# Sheet1.net
KiCad netlist of a schematic drawn in Altium Designer
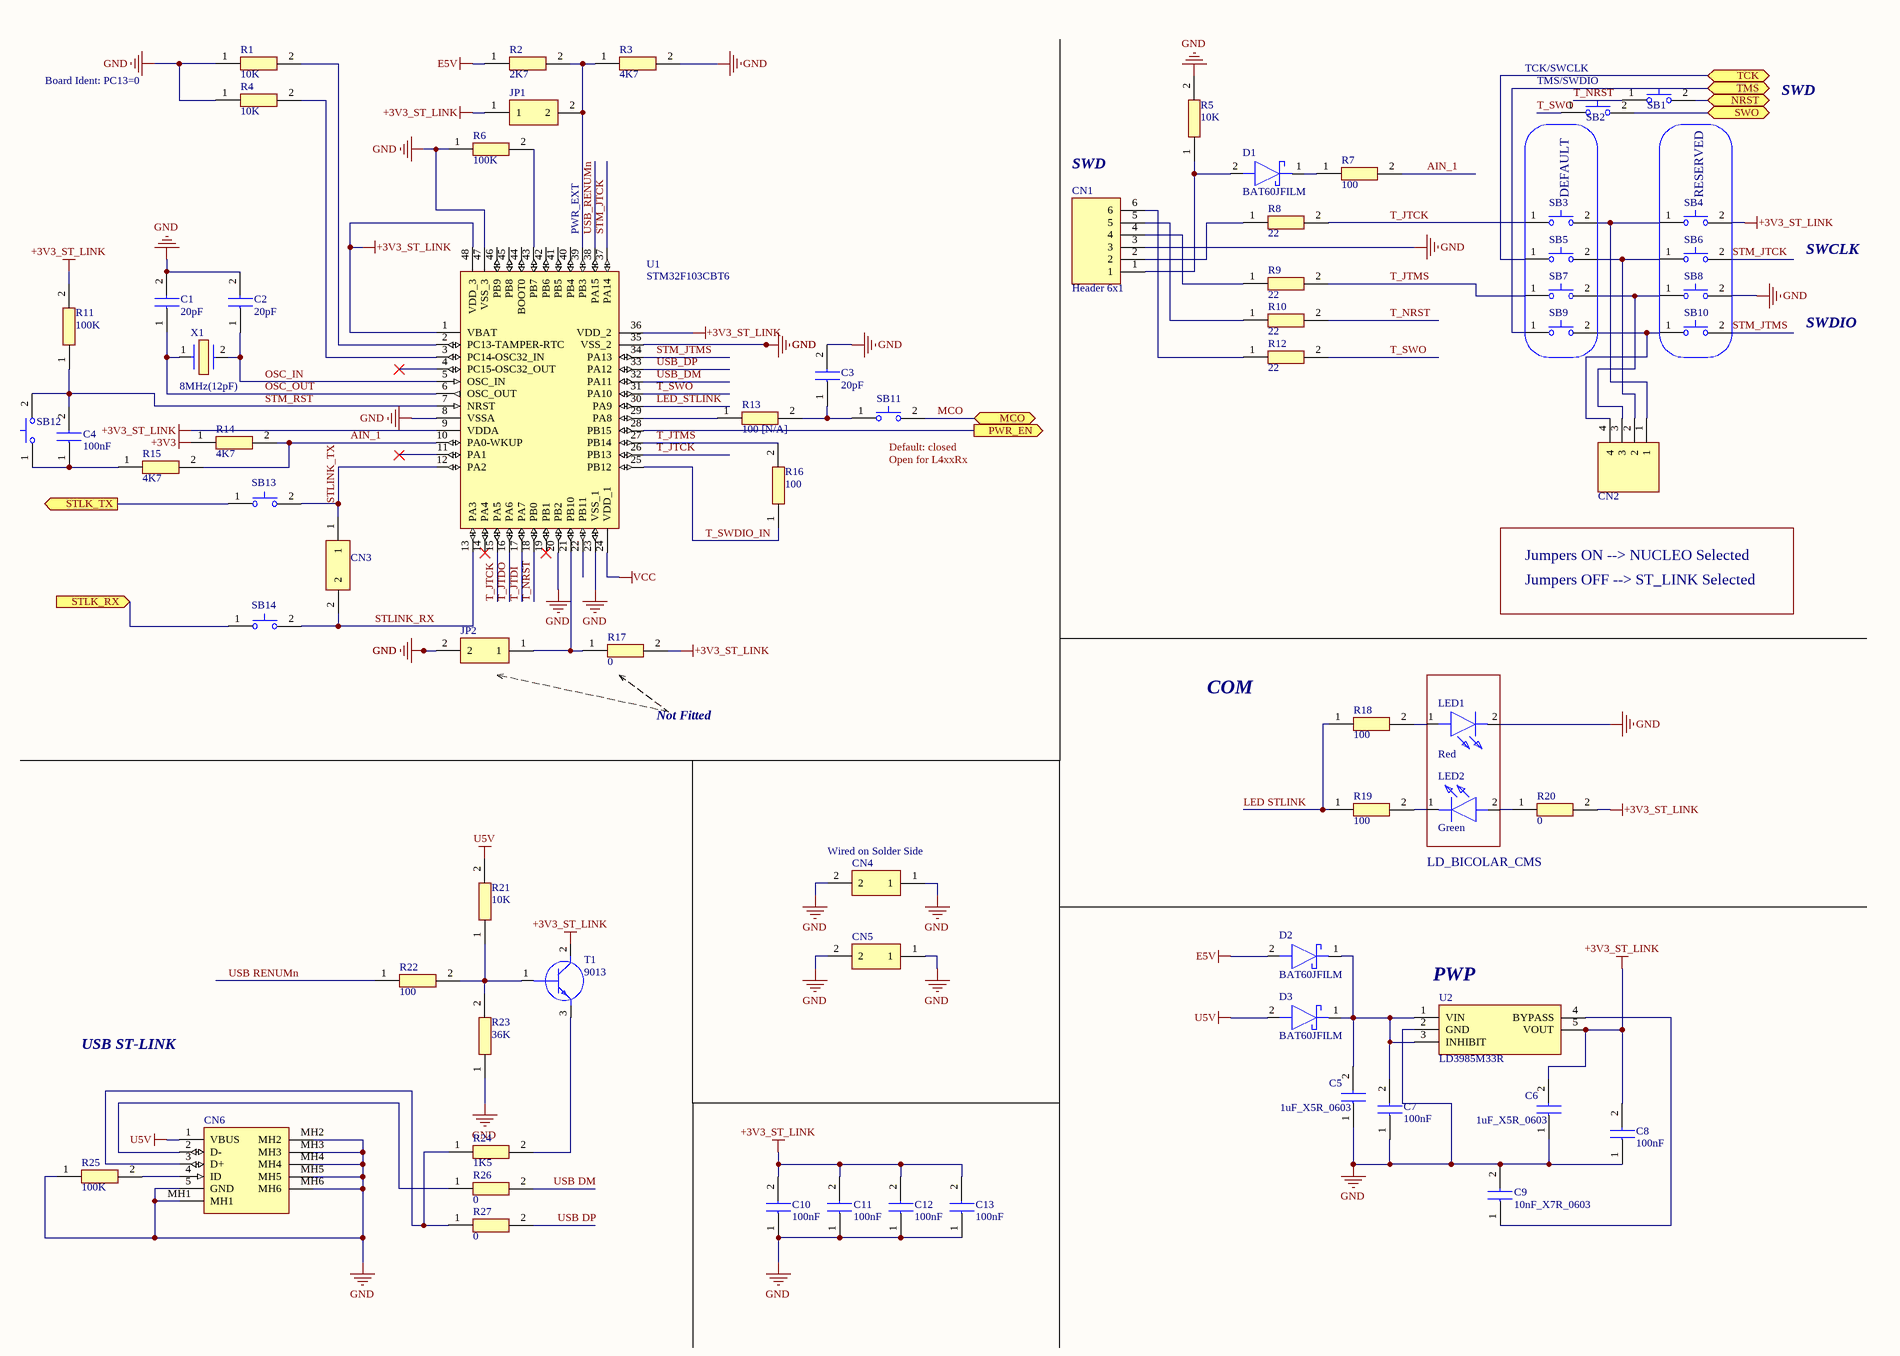
[diagram p0: Sheet1.SchDoc, right]

(export (version "E")
  (design (tool "Eeschema 10.0.6"))
  (components
    (comp (ref "C1")
      (value "20pF")
      (footprint "SamacSys:C1206")
      (description "Capacitor")
      (fields (field (name "MANUFACTURER_PART_NUMBER") "C1206C200KCGACTU"))
      (libsource (lib "*") (part "C1206C200KCGACTU"))
    )
    (comp (ref "C2")
      (value "20pF")
      (footprint "SamacSys:C1206")
      (description "Capacitor")
      (fields (field (name "MANUFACTURER_PART_NUMBER") "C1206C200KCGACTU"))
      (libsource (lib "*") (part "C1206C200KCGACTU"))
    )
    (comp (ref "C3")
      (value "20pF")
      (footprint "SamacSys:C1206")
      (description "Capacitor")
      (fields (field (name "MANUFACTURER_PART_NUMBER") "C1206C200KCGACTU"))
      (libsource (lib "*") (part "C1206C200KCGACTU"))
    )
    (comp (ref "C4")
      (value "100nF")
      (footprint "SamacSys:CAPC1608X90N")
      (description "Capacitor")
      (fields
        (field (name "MANUFACTURER_PART_NUMBER") "KAM15AR71H104KM")
        (field (name "MOUSER PART NUMBER") "581-KAM15AR71H104KM")
      )
      (libsource (lib "*") (part "KAM15AR71H104KM"))
    )
    (comp (ref "C5")
      (value "1uF_X5R_0603")
      (footprint "SamacSys:MAJx16")
      (description "Capacitor")
      (fields (field (name "MANUFACTURER_PART_NUMBER") "MAJCT168BB7105KTEA01"))
      (libsource (lib "*") (part "MAJCT168BB7105KTEA01"))
    )
    (comp (ref "C6")
      (value "1uF_X5R_0603")
      (footprint "SamacSys:MAJx16")
      (description "Capacitor")
      (fields (field (name "MANUFACTURER_PART_NUMBER") "MAJCT168BB7105KTEA01"))
      (libsource (lib "*") (part "MAJCT168BB7105KTEA01"))
    )
    (comp (ref "C7")
      (value "100nF")
      (footprint "SamacSys:CAPC1608X90N")
      (description "Capacitor")
      (fields
        (field (name "MANUFACTURER_PART_NUMBER") "KAM15AR71H104KM")
        (field (name "MOUSER PART NUMBER") "581-KAM15AR71H104KM")
      )
      (libsource (lib "*") (part "KAM15AR71H104KM"))
    )
    (comp (ref "C8")
      (value "100nF")
      (footprint "SamacSys:CAPC1608X90N")
      (description "Capacitor")
      (fields
        (field (name "MANUFACTURER_PART_NUMBER") "KAM15AR71H104KM")
        (field (name "MOUSER PART NUMBER") "581-KAM15AR71H104KM")
      )
      (libsource (lib "*") (part "KAM15AR71H104KM"))
    )
    (comp (ref "C9")
      (value "10nF_X7R_0603")
      (footprint "SamacSys:CAPC3316X145N")
      (description "Capacitor")
      (fields
        (field (name "MANUFACTURER_PART_NUMBER") "KGM31GCG2J103JU")
        (field (name "MOUSER PART NUMBER") "581-KGM31GCG2J103JU")
      )
      (libsource (lib "*") (part "KGM31GCG2J103JU"))
    )
    (comp (ref "C10")
      (value "100nF")
      (footprint "SamacSys:CAPC1608X90N")
      (description "Capacitor")
      (fields
        (field (name "MANUFACTURER_PART_NUMBER") "KAM15AR71H104KM")
        (field (name "MOUSER PART NUMBER") "581-KAM15AR71H104KM")
      )
      (libsource (lib "*") (part "KAM15AR71H104KM"))
    )
    (comp (ref "C11")
      (value "100nF")
      (footprint "SamacSys:CAPC1608X90N")
      (description "Capacitor")
      (fields
        (field (name "MANUFACTURER_PART_NUMBER") "KAM15AR71H104KM")
        (field (name "MOUSER PART NUMBER") "581-KAM15AR71H104KM")
      )
      (libsource (lib "*") (part "KAM15AR71H104KM"))
    )
    (comp (ref "C12")
      (value "100nF")
      (footprint "SamacSys:CAPC1608X90N")
      (description "Capacitor")
      (fields
        (field (name "MANUFACTURER_PART_NUMBER") "KAM15AR71H104KM")
        (field (name "MOUSER PART NUMBER") "581-KAM15AR71H104KM")
      )
      (libsource (lib "*") (part "KAM15AR71H104KM"))
    )
    (comp (ref "C13")
      (value "100nF")
      (footprint "SamacSys:CAPC1608X90N")
      (description "Capacitor")
      (fields
        (field (name "MANUFACTURER_PART_NUMBER") "KAM15AR71H104KM")
        (field (name "MOUSER PART NUMBER") "581-KAM15AR71H104KM")
      )
      (libsource (lib "*") (part "KAM15AR71H104KM"))
    )
    (comp (ref "CN1")
      (value "Header 6x1")
      (footprint "SamacSys:HDRV6W66P0X254_1X6_1524X249X838P")
      (description "Connector")
      (fields
        (field (name "MANUFACTURER_PART_NUMBER") "22-28-4062")
        (field (name "MOUSER PART NUMBER") "538-22-28-4062")
      )
      (libsource (lib "*") (part "22-28-4062"))
    )
    (comp (ref "CN2")
      (value "53014-0410")
      (footprint "SamacSys:SHDR4W60P0X200_1X4_1200X435X1000P")
      (description "Connector")
      (fields (field (name "MOUSER PART NUMBER") "538-53014-0410"))
      (libsource (lib "*") (part "53014-0410"))
    )
    (comp (ref "CN3")
      (value "3-647166-2")
      (footprint "SamacSys:36471662")
      (description "Connector")
      (fields (field (name "MOUSER PART NUMBER") "571-3-647166-2"))
      (libsource (lib "") (part "3-647166-2_1"))
    )
    (comp (ref "CN4")
      (value "3-647166-2")
      (footprint "SamacSys:36471662")
      (description "Connector")
      (fields (field (name "MOUSER PART NUMBER") "571-3-647166-2"))
      (libsource (lib "*") (part "3-647166-2"))
    )
    (comp (ref "CN5")
      (value "3-647166-2")
      (footprint "SamacSys:36471662")
      (description "Connector")
      (fields (field (name "MOUSER PART NUMBER") "571-3-647166-2"))
      (libsource (lib "*") (part "3-647166-2"))
    )
    (comp (ref "CN6")
      (value "204926-1103")
      (footprint "SamacSys:2049261103")
      (description "Connector")
      (fields (field (name "MOUSER PART NUMBER") "538-204926-1103"))
      (libsource (lib "*") (part "204926-1103"))
    )
    (comp (ref "D1")
      (value "BAT60JFILM")
      (footprint "SamacSys:SOD2513X117N")
      (description "Schottky Diode")
      (fields (field (name "MOUSER PART NUMBER") "511-BAT60JFILM"))
      (libsource (lib "*") (part "BAT60JFILM"))
    )
    (comp (ref "D2")
      (value "BAT60JFILM")
      (footprint "SamacSys:SOD2513X117N")
      (description "Schottky Diode")
      (fields (field (name "MOUSER PART NUMBER") "511-BAT60JFILM"))
      (libsource (lib "*") (part "BAT60JFILM"))
    )
    (comp (ref "D3")
      (value "BAT60JFILM")
      (footprint "SamacSys:SOD2513X117N")
      (description "Schottky Diode")
      (fields (field (name "MOUSER PART NUMBER") "511-BAT60JFILM"))
      (libsource (lib "*") (part "BAT60JFILM"))
    )
    (comp (ref "JP1")
      (value "3-647166-2")
      (footprint "SamacSys:36471662")
      (description "Connector")
      (fields (field (name "MOUSER PART NUMBER") "571-3-647166-2"))
      (libsource (lib "") (part "3-647166-2_2"))
    )
    (comp (ref "JP2")
      (value "3-647166-2")
      (footprint "SamacSys:36471662")
      (description "Connector")
      (fields (field (name "MOUSER PART NUMBER") "571-3-647166-2"))
      (libsource (lib "*") (part "3-647166-2"))
    )
    (comp (ref "LED1")
      (value "Red")
      (footprint "SamacSys:C4SMARGYCS4V1BB1")
      (description "LED")
      (fields
        (field (name "MANUFACTURER_PART_NUMBER") "C4SMA-RGY-CS4V1BB1")
        (field (name "MOUSER PART NUMBER") "941-C4SMARGYCS4V1BB1")
      )
      (libsource (lib "*") (part "C4SMA-RGY-CS4V1BB1"))
    )
    (comp (ref "LED2")
      (value "Green")
      (footprint "SamacSys:TLHG5420ASZ")
      (description "LED")
      (fields
        (field (name "MANUFACTURER_PART_NUMBER") "TLHG5420-ASZ")
        (field (name "MOUSER PART NUMBER") "78-TLHG5420-ASZ")
      )
      (libsource (lib "*") (part "TLHG5420-ASZ"))
    )
    (comp (ref "R1")
      (value "10K")
      (footprint "SamacSys:RESC6331X80N")
      (description "Resistor")
      (fields
        (field (name "MANUFACTURER_PART_NUMBER") "CRM2512QJW-103ELF")
        (field (name "MOUSER PART NUMBER") "652-CRM2512QJW-103E")
      )
      (libsource (lib "*") (part "CRM2512QJW-103ELF"))
    )
    (comp (ref "R2")
      (value "2K7")
      (footprint "SamacSys:RESC3225X70N")
      (description "Resistor")
      (fields
        (field (name "MANUFACTURER_PART_NUMBER") "CRCW12102K70FKEAHP")
        (field (name "MOUSER PART NUMBER") "71-CRCW12102K70FKEAH")
      )
      (libsource (lib "*") (part "CRCW12102K70FKEAHP"))
    )
    (comp (ref "R3")
      (value "4K7")
      (footprint "SamacSys:RESC1005X37N")
      (description "Resistor")
      (fields
        (field (name "MANUFACTURER_PART_NUMBER") "MCS04020D4701BE000")
        (field (name "MOUSER PART NUMBER") "594-MCS04020D4701BE0")
      )
      (libsource (lib "*") (part "MCS04020D4701BE000"))
    )
    (comp (ref "R4")
      (value "10K")
      (footprint "SamacSys:RESC6331X80N")
      (description "Resistor")
      (fields
        (field (name "MANUFACTURER_PART_NUMBER") "CRM2512QJW-103ELF")
        (field (name "MOUSER PART NUMBER") "652-CRM2512QJW-103E")
      )
      (libsource (lib "*") (part "CRM2512QJW-103ELF"))
    )
    (comp (ref "R5")
      (value "10K")
      (footprint "SamacSys:RESC6331X80N")
      (description "Resistor")
      (fields
        (field (name "MANUFACTURER_PART_NUMBER") "CRM2512QJW-103ELF")
        (field (name "MOUSER PART NUMBER") "652-CRM2512QJW-103E")
      )
      (libsource (lib "") (part "CRM2512QJW-103ELF_1"))
    )
    (comp (ref "R6")
      (value "100K")
      (footprint "SamacSys:RESC1005X40N")
      (description "Resistor")
      (fields
        (field (name "MANUFACTURER_PART_NUMBER") "SFR01MZPF1003")
        (field (name "MOUSER PART NUMBER") "755-SFR01MZPF1003")
      )
      (libsource (lib "*") (part "SFR01MZPF1003"))
    )
    (comp (ref "R7")
      (value "100")
      (footprint "SamacSys:RESC1005X37N")
      (description "Resistor")
      (fields
        (field (name "MANUFACTURER_PART_NUMBER") "MCS04020C1000FE000")
        (field (name "MOUSER PART NUMBER") "594-MCS04020C1000FE0")
      )
      (libsource (lib "*") (part "MCS04020C1000FE000"))
    )
    (comp (ref "R8")
      (value "22")
      (footprint "SamacSys:ERA6AEB1020V")
      (description "Resistor")
      (fields
        (field (name "MANUFACTURER_PART_NUMBER") "ERA-6AHD220V")
        (field (name "MOUSER PART NUMBER") "667-ERA-6AHD220V")
      )
      (libsource (lib "*") (part "ERA-6AHD220V"))
    )
    (comp (ref "R9")
      (value "22")
      (footprint "SamacSys:ERA6AEB1020V")
      (description "Resistor")
      (fields
        (field (name "MANUFACTURER_PART_NUMBER") "ERA-6AHD220V")
        (field (name "MOUSER PART NUMBER") "667-ERA-6AHD220V")
      )
      (libsource (lib "*") (part "ERA-6AHD220V"))
    )
    (comp (ref "R10")
      (value "22")
      (footprint "SamacSys:ERA6AEB1020V")
      (description "Resistor")
      (fields
        (field (name "MANUFACTURER_PART_NUMBER") "ERA-6AHD220V")
        (field (name "MOUSER PART NUMBER") "667-ERA-6AHD220V")
      )
      (libsource (lib "*") (part "ERA-6AHD220V"))
    )
    (comp (ref "R11")
      (value "100K")
      (footprint "SamacSys:RESC1005X40N")
      (description "Resistor")
      (fields
        (field (name "MANUFACTURER_PART_NUMBER") "SFR01MZPF1003")
        (field (name "MOUSER PART NUMBER") "755-SFR01MZPF1003")
      )
      (libsource (lib "") (part "SFR01MZPF1003_1"))
    )
    (comp (ref "R12")
      (value "22")
      (footprint "SamacSys:ERA6AEB1020V")
      (description "Resistor")
      (fields
        (field (name "MANUFACTURER_PART_NUMBER") "ERA-6AHD220V")
        (field (name "MOUSER PART NUMBER") "667-ERA-6AHD220V")
      )
      (libsource (lib "*") (part "ERA-6AHD220V"))
    )
    (comp (ref "R13")
      (value "100 [N/A]")
      (footprint "SamacSys:RESC1005X37N")
      (description "Resistor")
      (fields
        (field (name "MANUFACTURER_PART_NUMBER") "MCS04020C1000FE000")
        (field (name "MOUSER PART NUMBER") "594-MCS04020C1000FE0")
      )
      (libsource (lib "*") (part "MCS04020C1000FE000"))
    )
    (comp (ref "R14")
      (value "4K7")
      (footprint "SamacSys:RESC1005X37N")
      (description "Resistor")
      (fields
        (field (name "MANUFACTURER_PART_NUMBER") "MCS04020D4701BE000")
        (field (name "MOUSER PART NUMBER") "594-MCS04020D4701BE0")
      )
      (libsource (lib "*") (part "MCS04020D4701BE000"))
    )
    (comp (ref "R15")
      (value "4K7")
      (footprint "SamacSys:RESC1005X37N")
      (description "Resistor")
      (fields
        (field (name "MANUFACTURER_PART_NUMBER") "MCS04020D4701BE000")
        (field (name "MOUSER PART NUMBER") "594-MCS04020D4701BE0")
      )
      (libsource (lib "*") (part "MCS04020D4701BE000"))
    )
    (comp (ref "R16")
      (value "100")
      (footprint "SamacSys:RESC1005X37N")
      (description "Resistor")
      (fields
        (field (name "MANUFACTURER_PART_NUMBER") "MCS04020C1000FE000")
        (field (name "MOUSER PART NUMBER") "594-MCS04020C1000FE0")
      )
      (libsource (lib "") (part "MCS04020C1000FE000_1"))
    )
    (comp (ref "R17")
      (value "0")
      (footprint "SamacSys:RESC2013X84N")
      (description "Resistor")
      (fields
        (field (name "MANUFACTURER_PART_NUMBER") "WSL080500000ZEA9")
        (field (name "MOUSER PART NUMBER") "71-WSL080500000ZEA9")
      )
      (libsource (lib "*") (part "WSL080500000ZEA9"))
    )
    (comp (ref "R18")
      (value "100")
      (footprint "SamacSys:RESC1005X37N")
      (description "Resistor")
      (fields
        (field (name "MANUFACTURER_PART_NUMBER") "MCS04020C1000FE000")
        (field (name "MOUSER PART NUMBER") "594-MCS04020C1000FE0")
      )
      (libsource (lib "*") (part "MCS04020C1000FE000"))
    )
    (comp (ref "R19")
      (value "100")
      (footprint "SamacSys:RESC1005X37N")
      (description "Resistor")
      (fields
        (field (name "MANUFACTURER_PART_NUMBER") "MCS04020C1000FE000")
        (field (name "MOUSER PART NUMBER") "594-MCS04020C1000FE0")
      )
      (libsource (lib "*") (part "MCS04020C1000FE000"))
    )
    (comp (ref "R20")
      (value "0")
      (footprint "SamacSys:RESC2013X84N")
      (description "Resistor")
      (fields
        (field (name "MANUFACTURER_PART_NUMBER") "WSL080500000ZEA9")
        (field (name "MOUSER PART NUMBER") "71-WSL080500000ZEA9")
      )
      (libsource (lib "*") (part "WSL080500000ZEA9"))
    )
    (comp (ref "R21")
      (value "10K")
      (footprint "SamacSys:RESC6331X80N")
      (description "Resistor")
      (fields
        (field (name "MANUFACTURER_PART_NUMBER") "CRM2512QJW-103ELF")
        (field (name "MOUSER PART NUMBER") "652-CRM2512QJW-103E")
      )
      (libsource (lib "") (part "CRM2512QJW-103ELF_1"))
    )
    (comp (ref "R22")
      (value "100")
      (footprint "SamacSys:RESC1005X37N")
      (description "Resistor")
      (fields
        (field (name "MANUFACTURER_PART_NUMBER") "MCS04020C1000FE000")
        (field (name "MOUSER PART NUMBER") "594-MCS04020C1000FE0")
      )
      (libsource (lib "*") (part "MCS04020C1000FE000"))
    )
    (comp (ref "R23")
      (value "36K")
      (footprint "SamacSys:RESC2012X55N")
      (description "Resistor")
      (fields (field (name "MANUFACTURER_PART_NUMBER") "TNPW080536K0BEEA"))
      (libsource (lib "*") (part "TNPW080536K0BEEA"))
    )
    (comp (ref "R24")
      (value "1K5")
      (footprint "SamacSys:RESC3116X65N")
      (description "Resistor")
      (fields
        (field (name "MANUFACTURER_PART_NUMBER") "CRCW12061K50FKEAHP")
        (field (name "MOUSER PART NUMBER") "71-CRCW12061K50FKEAH")
      )
      (libsource (lib "*") (part "CRCW12061K50FKEAHP"))
    )
    (comp (ref "R25")
      (value "100K")
      (footprint "SamacSys:RESC1005X40N")
      (description "Resistor")
      (fields
        (field (name "MANUFACTURER_PART_NUMBER") "SFR01MZPF1003")
        (field (name "MOUSER PART NUMBER") "755-SFR01MZPF1003")
      )
      (libsource (lib "*") (part "SFR01MZPF1003"))
    )
    (comp (ref "R26")
      (value "0")
      (footprint "SamacSys:RESC2013X84N")
      (description "Resistor")
      (fields
        (field (name "MANUFACTURER_PART_NUMBER") "WSL080500000ZEA9")
        (field (name "MOUSER PART NUMBER") "71-WSL080500000ZEA9")
      )
      (libsource (lib "*") (part "WSL080500000ZEA9"))
    )
    (comp (ref "R27")
      (value "0")
      (footprint "SamacSys:RESC2013X84N")
      (description "Resistor")
      (fields
        (field (name "MANUFACTURER_PART_NUMBER") "WSL080500000ZEA9")
        (field (name "MOUSER PART NUMBER") "71-WSL080500000ZEA9")
      )
      (libsource (lib "*") (part "WSL080500000ZEA9"))
    )
    (comp (ref "SB1")
      (value "8631CQD2")
      (footprint "SamacSys:8631CQD2")
      (description "Switch (2-Pin Push)")
      (fields (field (name "MOUSER PART NUMBER") "611-8631-261"))
      (libsource (lib "*") (part "8631CQD2"))
    )
    (comp (ref "SB2")
      (value "8631CQD2")
      (footprint "SamacSys:8631CQD2")
      (description "Switch (2-Pin Push)")
      (fields (field (name "MOUSER PART NUMBER") "611-8631-261"))
      (libsource (lib "*") (part "8631CQD2"))
    )
    (comp (ref "SB3")
      (value "8631CQD2")
      (footprint "SamacSys:8631CQD2")
      (description "Switch (2-Pin Push)")
      (fields (field (name "MOUSER PART NUMBER") "611-8631-261"))
      (libsource (lib "*") (part "8631CQD2"))
    )
    (comp (ref "SB4")
      (value "8631CQD2")
      (footprint "SamacSys:8631CQD2")
      (description "Switch (2-Pin Push)")
      (fields (field (name "MOUSER PART NUMBER") "611-8631-261"))
      (libsource (lib "*") (part "8631CQD2"))
    )
    (comp (ref "SB5")
      (value "8631CQD2")
      (footprint "SamacSys:8631CQD2")
      (description "Switch (2-Pin Push)")
      (fields (field (name "MOUSER PART NUMBER") "611-8631-261"))
      (libsource (lib "*") (part "8631CQD2"))
    )
    (comp (ref "SB6")
      (value "8631CQD2")
      (footprint "SamacSys:8631CQD2")
      (description "Switch (2-Pin Push)")
      (fields (field (name "MOUSER PART NUMBER") "611-8631-261"))
      (libsource (lib "*") (part "8631CQD2"))
    )
    (comp (ref "SB7")
      (value "8631CQD2")
      (footprint "SamacSys:8631CQD2")
      (description "Switch (2-Pin Push)")
      (fields (field (name "MOUSER PART NUMBER") "611-8631-261"))
      (libsource (lib "*") (part "8631CQD2"))
    )
    (comp (ref "SB8")
      (value "8631CQD2")
      (footprint "SamacSys:8631CQD2")
      (description "Switch (2-Pin Push)")
      (fields (field (name "MOUSER PART NUMBER") "611-8631-261"))
      (libsource (lib "*") (part "8631CQD2"))
    )
    (comp (ref "SB9")
      (value "8631CQD2")
      (footprint "SamacSys:8631CQD2")
      (description "Switch (2-Pin Push)")
      (fields (field (name "MOUSER PART NUMBER") "611-8631-261"))
      (libsource (lib "*") (part "8631CQD2"))
    )
    (comp (ref "SB10")
      (value "8631CQD2")
      (footprint "SamacSys:8631CQD2")
      (description "Switch (2-Pin Push)")
      (fields (field (name "MOUSER PART NUMBER") "611-8631-261"))
      (libsource (lib "*") (part "8631CQD2"))
    )
    (comp (ref "SB11")
      (value "8631CQD2")
      (footprint "SamacSys:8631CQD2")
      (description "Switch (2-Pin Push)")
      (fields (field (name "MOUSER PART NUMBER") "611-8631-261"))
      (libsource (lib "*") (part "8631CQD2"))
    )
    (comp (ref "SB12")
      (value "8631CQD2")
      (footprint "SamacSys:8631CQD2")
      (description "Switch (2-Pin Push)")
      (fields (field (name "MOUSER PART NUMBER") "611-8631-261"))
      (libsource (lib "*") (part "8631CQD2"))
    )
    (comp (ref "SB13")
      (value "8631CQD2")
      (footprint "SamacSys:8631CQD2")
      (description "Switch (2-Pin Push)")
      (fields (field (name "MOUSER PART NUMBER") "611-8631-261"))
      (libsource (lib "*") (part "8631CQD2"))
    )
    (comp (ref "SB14")
      (value "8631CQD2")
      (footprint "SamacSys:8631CQD2")
      (description "Switch (2-Pin Push)")
      (fields (field (name "MOUSER PART NUMBER") "611-8631-261"))
      (libsource (lib "*") (part "8631CQD2"))
    )
    (comp (ref "T1")
      (value "9013")
      (footprint "SamacSys:TO254P290X760X1320-3P")
      (description "Transistor BJT NPN")
      (fields
        (field (name "MANUFACTURER_PART_NUMBER") "BD139")
        (field (name "MOUSER PART NUMBER") "511-BD139")
      )
      (libsource (lib "*") (part "BD139"))
    )
    (comp (ref "U1")
      (value "STM32F103CBT6")
      (footprint "SamacSys:QFP50P900X900X160-48N")
      (description "Integrated Circuit")
      (fields (field (name "MOUSER PART NUMBER") "511-STM32F103CBT6"))
      (libsource (lib "*") (part "STM32F103CBT6"))
    )
    (comp (ref "U2")
      (value "LD3985M33R")
      (footprint "SamacSys:SOT95P280X145-5N")
      (description "Integrated Circuit")
      (fields (field (name "MOUSER PART NUMBER") "511-LD3985M33R"))
      (libsource (lib "*") (part "LD3985M33R"))
    )
    (comp (ref "X1")
      (value "8MHz(12pF)")
      (footprint "SamacSys:ECS80125PXGMTR")
      (description "Crystal or Oscillator")
      (fields
        (field (name "MANUFACTURER_PART_NUMBER") "ECS-80-12-5PX-GM-TR")
        (field (name "MOUSER PART NUMBER") "520-80-12-5PX-GM-TR")
      )
      (libsource (lib "*") (part "ECS-80-12-5PX-GM-TR"))
    )
  )
  (nets
    (net (code "1") (name "+3V3") (class "Default")
      (node (ref "R14") (pin "1") (pinfunction "1_1") (pintype "passive"))
    )
    (net (code "2") (name "+3V3_ST_LINK") (class "Default")
      (node (ref "C10") (pin "2") (pinfunction "2_2") (pintype "passive"))
      (node (ref "C11") (pin "2") (pinfunction "2_2") (pintype "passive"))
      (node (ref "C12") (pin "2") (pinfunction "2_2") (pintype "passive"))
      (node (ref "C13") (pin "2") (pinfunction "2_2") (pintype "passive"))
      (node (ref "C6") (pin "2") (pinfunction "2_2") (pintype "passive"))
      (node (ref "C8") (pin "2") (pinfunction "2_2") (pintype "passive"))
      (node (ref "JP1") (pin "1") (pinfunction "1_1") (pintype "passive"))
      (node (ref "R11") (pin "2") (pinfunction "2_2") (pintype "passive"))
      (node (ref "R17") (pin "2") (pinfunction "2_2") (pintype "passive"))
      (node (ref "R20") (pin "2") (pinfunction "2_2") (pintype "passive"))
      (node (ref "SB4") (pin "2") (pinfunction "N.O._2_2") (pintype "passive"))
      (node (ref "T1") (pin "2") (pinfunction "C_2") (pintype "passive"))
      (node (ref "U1") (pin "1") (pinfunction "VBAT_1") (pintype "passive"))
      (node (ref "U1") (pin "36") (pinfunction "VDD_2_36") (pintype "passive"))
      (node (ref "U1") (pin "48") (pinfunction "VDD_3_48") (pintype "passive"))
      (node (ref "U1") (pin "9") (pinfunction "VDDA_9") (pintype "passive"))
      (node (ref "U2") (pin "5") (pinfunction "VOUT_5") (pintype "passive"))
    )
    (net (code "3") (name "/AIN_1") (class "Default")
      (node (ref "R14") (pin "2") (pinfunction "2_2") (pintype "passive"))
      (node (ref "R15") (pin "2") (pinfunction "2_2") (pintype "passive"))
      (node (ref "R7") (pin "2") (pinfunction "2_2") (pintype "passive"))
      (node (ref "U1") (pin "10") (pinfunction "PA0-WKUP_10") (pintype "bidirectional"))
    )
    (net (code "4") (name "/LED STLINK") (class "Default")
      (node (ref "R18") (pin "1") (pinfunction "1_1") (pintype "passive"))
      (node (ref "R19") (pin "1") (pinfunction "1_1") (pintype "passive"))
    )
    (net (code "5") (name "/LED_STLINK") (class "Default")
      (node (ref "U1") (pin "30") (pinfunction "PA9_30") (pintype "bidirectional"))
    )
    (net (code "6") (name "/MCO") (class "Default")
      (node (ref "SB11") (pin "2") (pinfunction "N.O._2_2") (pintype "passive"))
    )
    (net (code "7") (name "/NRST") (class "Default")
      (node (ref "SB1") (pin "2") (pinfunction "N.O._2_2") (pintype "passive"))
    )
    (net (code "8") (name "/OSC_IN") (class "Default")
      (node (ref "C2") (pin "1") (pinfunction "1_1") (pintype "passive"))
      (node (ref "U1") (pin "5") (pinfunction "OSC_IN_5") (pintype "input"))
      (node (ref "X1") (pin "2") (pinfunction "2_2") (pintype "passive"))
    )
    (net (code "9") (name "/OSC_OUT") (class "Default")
      (node (ref "C1") (pin "1") (pinfunction "1_1") (pintype "passive"))
      (node (ref "U1") (pin "6") (pinfunction "OSC_OUT_6") (pintype "output"))
      (node (ref "X1") (pin "1") (pinfunction "1_1") (pintype "passive"))
    )
    (net (code "10") (name "/PWR_EN") (class "Default")
      (node (ref "U1") (pin "28") (pinfunction "PB15_28") (pintype "bidirectional"))
    )
    (net (code "11") (name "/STLINK_RX") (class "Default")
      (node (ref "CN3") (pin "2") (pinfunction "2_2") (pintype "passive"))
      (node (ref "SB14") (pin "2") (pinfunction "N.O._2_2") (pintype "passive"))
      (node (ref "U1") (pin "13") (pinfunction "PA3_13") (pintype "bidirectional"))
    )
    (net (code "12") (name "/STLINK_TX") (class "Default")
      (node (ref "CN3") (pin "1") (pinfunction "1_1") (pintype "passive"))
      (node (ref "SB13") (pin "2") (pinfunction "N.O._2_2") (pintype "passive"))
      (node (ref "U1") (pin "12") (pinfunction "PA2_12") (pintype "bidirectional"))
    )
    (net (code "13") (name "/STLK_RX") (class "Default")
      (node (ref "SB14") (pin "1") (pinfunction "N.O._1_1") (pintype "passive"))
    )
    (net (code "14") (name "/STLK_TX") (class "Default")
      (node (ref "SB13") (pin "1") (pinfunction "N.O._1_1") (pintype "passive"))
    )
    (net (code "15") (name "/STM_JTCK") (class "Default")
      (node (ref "SB6") (pin "2") (pinfunction "N.O._2_2") (pintype "passive"))
      (node (ref "U1") (pin "37") (pinfunction "PA14_37") (pintype "bidirectional"))
    )
    (net (code "16") (name "/STM_JTMS") (class "Default")
      (node (ref "SB10") (pin "2") (pinfunction "N.O._2_2") (pintype "passive"))
      (node (ref "U1") (pin "34") (pinfunction "PA13_34") (pintype "bidirectional"))
    )
    (net (code "17") (name "/STM_RST") (class "Default")
      (node (ref "C4") (pin "2") (pinfunction "2_2") (pintype "passive"))
      (node (ref "R11") (pin "1") (pinfunction "1_1") (pintype "passive"))
      (node (ref "SB12") (pin "2") (pinfunction "N.O._2_2") (pintype "passive"))
      (node (ref "U1") (pin "7") (pinfunction "NRST_7") (pintype "input"))
    )
    (net (code "18") (name "/SWO") (class "Default")
      (node (ref "SB2") (pin "2") (pinfunction "N.O._2_2") (pintype "passive"))
    )
    (net (code "19") (name "/TCK") (class "Default")
      (node (ref "SB5") (pin "1") (pinfunction "N.O._1_1") (pintype "passive"))
    )
    (net (code "20") (name "/TMS") (class "Default")
      (node (ref "SB9") (pin "1") (pinfunction "N.O._1_1") (pintype "passive"))
    )
    (net (code "21") (name "/T_JTCK") (class "Default")
      (node (ref "R8") (pin "2") (pinfunction "2_2") (pintype "passive"))
      (node (ref "SB3") (pin "1") (pinfunction "N.O._1_1") (pintype "passive"))
      (node (ref "U1") (pin "15") (pinfunction "PA5_15") (pintype "bidirectional"))
      (node (ref "U1") (pin "26") (pinfunction "PB13_26") (pintype "bidirectional"))
    )
    (net (code "22") (name "/T_JTDI") (class "Default")
      (node (ref "U1") (pin "17") (pinfunction "PA7_17") (pintype "bidirectional"))
    )
    (net (code "23") (name "/T_JTDO") (class "Default")
      (node (ref "U1") (pin "16") (pinfunction "PA6_16") (pintype "bidirectional"))
    )
    (net (code "24") (name "/T_JTMS") (class "Default")
      (node (ref "R16") (pin "2") (pinfunction "2_2") (pintype "passive"))
      (node (ref "R9") (pin "2") (pinfunction "2_2") (pintype "passive"))
      (node (ref "SB7") (pin "1") (pinfunction "N.O._1_1") (pintype "passive"))
      (node (ref "U1") (pin "27") (pinfunction "PB14_27") (pintype "bidirectional"))
    )
    (net (code "25") (name "/T_NRST") (class "Default")
      (node (ref "R10") (pin "2") (pinfunction "2_2") (pintype "passive"))
      (node (ref "SB1") (pin "1") (pinfunction "N.O._1_1") (pintype "passive"))
      (node (ref "U1") (pin "18") (pinfunction "PB0_18") (pintype "bidirectional"))
    )
    (net (code "26") (name "/T_SWDIO_IN") (class "Default")
      (node (ref "R16") (pin "1") (pinfunction "1_1") (pintype "passive"))
      (node (ref "U1") (pin "25") (pinfunction "PB12_25") (pintype "bidirectional"))
    )
    (net (code "27") (name "/T_SWO") (class "Default")
      (node (ref "R12") (pin "2") (pinfunction "2_2") (pintype "passive"))
      (node (ref "SB2") (pin "1") (pinfunction "N.O._1_1") (pintype "passive"))
      (node (ref "U1") (pin "31") (pinfunction "PA10_31") (pintype "bidirectional"))
    )
    (net (code "28") (name "/USB DM") (class "Default")
      (node (ref "R26") (pin "2") (pinfunction "2_2") (pintype "passive"))
    )
    (net (code "29") (name "/USB DP") (class "Default")
      (node (ref "R27") (pin "2") (pinfunction "2_2") (pintype "passive"))
    )
    (net (code "30") (name "/USB RENUMn") (class "Default")
      (node (ref "R22") (pin "1") (pinfunction "1_1") (pintype "passive"))
    )
    (net (code "31") (name "/USB_DM") (class "Default")
      (node (ref "U1") (pin "32") (pinfunction "PA11_32") (pintype "bidirectional"))
    )
    (net (code "32") (name "/USB_DP") (class "Default")
      (node (ref "U1") (pin "33") (pinfunction "PA12_33") (pintype "bidirectional"))
    )
    (net (code "33") (name "/USB_RENUMn") (class "Default")
      (node (ref "U1") (pin "38") (pinfunction "PA15_38") (pintype "bidirectional"))
    )
    (net (code "34") (name "E5V") (class "Default")
      (node (ref "D2") (pin "2") (pinfunction "A_2") (pintype "passive"))
      (node (ref "R2") (pin "1") (pinfunction "1_1") (pintype "passive"))
    )
    (net (code "35") (name "GND") (class "Default")
      (node (ref "C1") (pin "2") (pinfunction "2_2") (pintype "passive"))
      (node (ref "C10") (pin "1") (pinfunction "1_1") (pintype "passive"))
      (node (ref "C11") (pin "1") (pinfunction "1_1") (pintype "passive"))
      (node (ref "C12") (pin "1") (pinfunction "1_1") (pintype "passive"))
      (node (ref "C13") (pin "1") (pinfunction "1_1") (pintype "passive"))
      (node (ref "C2") (pin "2") (pinfunction "2_2") (pintype "passive"))
      (node (ref "C3") (pin "2") (pinfunction "2_2") (pintype "passive"))
      (node (ref "C5") (pin "1") (pinfunction "1_1") (pintype "passive"))
      (node (ref "C6") (pin "1") (pinfunction "1_1") (pintype "passive"))
      (node (ref "C7") (pin "1") (pinfunction "1_1") (pintype "passive"))
      (node (ref "C8") (pin "1") (pinfunction "1_1") (pintype "passive"))
      (node (ref "C9") (pin "2") (pinfunction "2_2") (pintype "passive"))
      (node (ref "CN1") (pin "3") (pinfunction "3_3") (pintype "passive"))
      (node (ref "CN4") (pin "1") (pinfunction "1_1") (pintype "passive"))
      (node (ref "CN4") (pin "2") (pinfunction "2_2") (pintype "passive"))
      (node (ref "CN5") (pin "1") (pinfunction "1_1") (pintype "passive"))
      (node (ref "CN5") (pin "2") (pinfunction "2_2") (pintype "passive"))
      (node (ref "CN6") (pin "5") (pinfunction "GND_5") (pintype "passive"))
      (node (ref "CN6") (pin "MH1") (pinfunction "MH1_MH1") (pintype "passive"))
      (node (ref "CN6") (pin "MH2") (pinfunction "MH2_MH2") (pintype "passive"))
      (node (ref "CN6") (pin "MH3") (pinfunction "MH3_MH3") (pintype "passive"))
      (node (ref "CN6") (pin "MH4") (pinfunction "MH4_MH4") (pintype "passive"))
      (node (ref "CN6") (pin "MH5") (pinfunction "MH5_MH5") (pintype "passive"))
      (node (ref "CN6") (pin "MH6") (pinfunction "MH6_MH6") (pintype "passive"))
      (node (ref "JP2") (pin "2") (pinfunction "2_2") (pintype "passive"))
      (node (ref "LED1") (pin "2") (pinfunction "K_2") (pintype "passive"))
      (node (ref "R1") (pin "1") (pinfunction "1_1") (pintype "passive"))
      (node (ref "R23") (pin "1") (pinfunction "1_1") (pintype "passive"))
      (node (ref "R25") (pin "1") (pinfunction "1_1") (pintype "passive"))
      (node (ref "R3") (pin "2") (pinfunction "2_2") (pintype "passive"))
      (node (ref "R4") (pin "1") (pinfunction "1_1") (pintype "passive"))
      (node (ref "R5") (pin "2") (pinfunction "2_2") (pintype "passive"))
      (node (ref "R6") (pin "1") (pinfunction "1_1") (pintype "passive"))
      (node (ref "SB8") (pin "2") (pinfunction "N.O._2_2") (pintype "passive"))
      (node (ref "U1") (pin "20") (pinfunction "PB2_20") (pintype "bidirectional"))
      (node (ref "U1") (pin "23") (pinfunction "VSS_1_23") (pintype "bidirectional"))
      (node (ref "U1") (pin "35") (pinfunction "VSS_2_35") (pintype "passive"))
      (node (ref "U1") (pin "47") (pinfunction "VSS_3_47") (pintype "passive"))
      (node (ref "U1") (pin "8") (pinfunction "VSSA_8") (pintype "passive"))
      (node (ref "U2") (pin "2") (pinfunction "GND_2") (pintype "passive"))
    )
    (net (code "36") (name "Net-(CN1-Pad2)") (class "Default")
      (node (ref "CN1") (pin "2") (pinfunction "2_2") (pintype "passive"))
      (node (ref "R8") (pin "1") (pinfunction "1_1") (pintype "passive"))
    )
    (net (code "37") (name "Net-(CN1-Pad4)") (class "Default")
      (node (ref "CN1") (pin "4") (pinfunction "4_4") (pintype "passive"))
      (node (ref "R9") (pin "1") (pinfunction "1_1") (pintype "passive"))
    )
    (net (code "38") (name "Net-(CN1-Pad5)") (class "Default")
      (node (ref "CN1") (pin "5") (pinfunction "5_5") (pintype "passive"))
      (node (ref "R10") (pin "1") (pinfunction "1_1") (pintype "passive"))
    )
    (net (code "39") (name "Net-(CN1-Pad6)") (class "Default")
      (node (ref "CN1") (pin "6") (pinfunction "6_6") (pintype "passive"))
      (node (ref "R12") (pin "1") (pinfunction "1_1") (pintype "passive"))
    )
    (net (code "40") (name "Net-(CN6-D+)") (class "Default")
      (node (ref "CN6") (pin "3") (pinfunction "D+_3") (pintype "bidirectional"))
      (node (ref "R24") (pin "1") (pinfunction "1_1") (pintype "passive"))
      (node (ref "R27") (pin "1") (pinfunction "1_1") (pintype "passive"))
    )
    (net (code "41") (name "Net-(CN6-D-)") (class "Default")
      (node (ref "CN6") (pin "2") (pinfunction "D-_2") (pintype "bidirectional"))
      (node (ref "R26") (pin "1") (pinfunction "1_1") (pintype "passive"))
    )
    (net (code "42") (name "Net-(CN6-ID)") (class "Default")
      (node (ref "CN6") (pin "4") (pinfunction "ID_4") (pintype "input"))
      (node (ref "R25") (pin "2") (pinfunction "2_2") (pintype "passive"))
    )
    (net (code "43") (name "Net-(D1-A)") (class "Default")
      (node (ref "CN1") (pin "1") (pinfunction "1_1") (pintype "passive"))
      (node (ref "D1") (pin "2") (pinfunction "A_2") (pintype "passive"))
      (node (ref "R5") (pin "1") (pinfunction "1_1") (pintype "passive"))
    )
    (net (code "44") (name "Net-(D1-K)") (class "Default")
      (node (ref "D1") (pin "1") (pinfunction "K_1") (pintype "passive"))
      (node (ref "R7") (pin "1") (pinfunction "1_1") (pintype "passive"))
    )
    (net (code "45") (name "Net-(D2-K)") (class "Default")
      (node (ref "C5") (pin "2") (pinfunction "2_2") (pintype "passive"))
      (node (ref "C7") (pin "2") (pinfunction "2_2") (pintype "passive"))
      (node (ref "D2") (pin "1") (pinfunction "K_1") (pintype "passive"))
      (node (ref "D3") (pin "1") (pinfunction "K_1") (pintype "passive"))
      (node (ref "U2") (pin "1") (pinfunction "VIN_1") (pintype "passive"))
      (node (ref "U2") (pin "3") (pinfunction "INHIBIT_3") (pintype "passive"))
    )
    (net (code "46") (name "Net-(LED1-A)") (class "Default")
      (node (ref "LED1") (pin "1") (pinfunction "A_1") (pintype "passive"))
      (node (ref "R18") (pin "2") (pinfunction "2_2") (pintype "passive"))
    )
    (net (code "47") (name "Net-(LED2-A)") (class "Default")
      (node (ref "LED2") (pin "2") (pinfunction "A_2") (pintype "passive"))
      (node (ref "R20") (pin "1") (pinfunction "1_1") (pintype "passive"))
    )
    (net (code "48") (name "Net-(LED2-K)") (class "Default")
      (node (ref "LED2") (pin "1") (pinfunction "K_1") (pintype "passive"))
      (node (ref "R19") (pin "2") (pinfunction "2_2") (pintype "passive"))
    )
    (net (code "49") (name "Net-(SB3-N.O._2)") (class "Default")
      (node (ref "CN2") (pin "1") (pinfunction "1_1") (pintype "passive"))
      (node (ref "SB3") (pin "2") (pinfunction "N.O._2_2") (pintype "passive"))
      (node (ref "SB4") (pin "1") (pinfunction "N.O._1_1") (pintype "passive"))
    )
    (net (code "50") (name "Net-(SB5-N.O._2)") (class "Default")
      (node (ref "CN2") (pin "2") (pinfunction "2_2") (pintype "passive"))
      (node (ref "SB5") (pin "2") (pinfunction "N.O._2_2") (pintype "passive"))
      (node (ref "SB6") (pin "1") (pinfunction "N.O._1_1") (pintype "passive"))
    )
    (net (code "51") (name "Net-(SB7-N.O._2)") (class "Default")
      (node (ref "CN2") (pin "3") (pinfunction "3_3") (pintype "passive"))
      (node (ref "SB7") (pin "2") (pinfunction "N.O._2_2") (pintype "passive"))
      (node (ref "SB8") (pin "1") (pinfunction "N.O._1_1") (pintype "passive"))
    )
    (net (code "52") (name "Net-(SB10-N.O._1)") (class "Default")
      (node (ref "CN2") (pin "4") (pinfunction "4_4") (pintype "passive"))
      (node (ref "SB10") (pin "1") (pinfunction "N.O._1_1") (pintype "passive"))
      (node (ref "SB9") (pin "2") (pinfunction "N.O._2_2") (pintype "passive"))
    )
    (net (code "53") (name "Net-(SB11-N.O._1)") (class "Default")
      (node (ref "C3") (pin "1") (pinfunction "1_1") (pintype "passive"))
      (node (ref "R13") (pin "2") (pinfunction "2_2") (pintype "passive"))
      (node (ref "SB11") (pin "1") (pinfunction "N.O._1_1") (pintype "passive"))
    )
    (net (code "54") (name "Net-(SB12-N.O._1)") (class "Default")
      (node (ref "C4") (pin "1") (pinfunction "1_1") (pintype "passive"))
      (node (ref "R15") (pin "1") (pinfunction "1_1") (pintype "passive"))
      (node (ref "SB12") (pin "1") (pinfunction "N.O._1_1") (pintype "passive"))
    )
    (net (code "55") (name "Net-(T1-B)") (class "Default")
      (node (ref "R21") (pin "1") (pinfunction "1_1") (pintype "passive"))
      (node (ref "R22") (pin "2") (pinfunction "2_2") (pintype "passive"))
      (node (ref "R23") (pin "2") (pinfunction "2_2") (pintype "passive"))
      (node (ref "T1") (pin "1") (pinfunction "B_1") (pintype "passive"))
    )
    (net (code "56") (name "Net-(T1-E)") (class "Default")
      (node (ref "R24") (pin "2") (pinfunction "2_2") (pintype "passive"))
      (node (ref "T1") (pin "3") (pinfunction "E_3") (pintype "passive"))
    )
    (net (code "57") (name "Net-(U1-PA8)") (class "Default")
      (node (ref "R13") (pin "1") (pinfunction "1_1") (pintype "passive"))
      (node (ref "U1") (pin "29") (pinfunction "PA8_29") (pintype "bidirectional"))
    )
    (net (code "58") (name "Net-(U1-PB3)") (class "Default")
      (node (ref "JP1") (pin "2") (pinfunction "2_2") (pintype "passive"))
      (node (ref "R2") (pin "2") (pinfunction "2_2") (pintype "passive"))
      (node (ref "R3") (pin "1") (pinfunction "1_1") (pintype "passive"))
      (node (ref "U1") (pin "39") (pinfunction "PB3_39") (pintype "bidirectional"))
    )
    (net (code "59") (name "Net-(U1-PB7)") (class "Default")
      (node (ref "R6") (pin "2") (pinfunction "2_2") (pintype "passive"))
      (node (ref "U1") (pin "43") (pinfunction "PB7_43") (pintype "bidirectional"))
    )
    (net (code "60") (name "Net-(U1-PB10)") (class "Default")
      (node (ref "JP2") (pin "1") (pinfunction "1_1") (pintype "passive"))
      (node (ref "R17") (pin "1") (pinfunction "1_1") (pintype "passive"))
      (node (ref "U1") (pin "21") (pinfunction "PB10_21") (pintype "bidirectional"))
    )
    (net (code "61") (name "Net-(U1-PC13-TAMPER-RTC)") (class "Default")
      (node (ref "R1") (pin "2") (pinfunction "2_2") (pintype "passive"))
      (node (ref "U1") (pin "2") (pinfunction "PC13-TAMPER-RTC_2") (pintype "bidirectional"))
    )
    (net (code "62") (name "Net-(U1-PC14-OSC32_IN)") (class "Default")
      (node (ref "R4") (pin "2") (pinfunction "2_2") (pintype "passive"))
      (node (ref "U1") (pin "3") (pinfunction "PC14-OSC32_IN_3") (pintype "bidirectional"))
    )
    (net (code "63") (name "Net-(U2-BYPASS)") (class "Default")
      (node (ref "C9") (pin "1") (pinfunction "1_1") (pintype "passive"))
      (node (ref "U2") (pin "4") (pinfunction "BYPASS_4") (pintype "passive"))
    )
    (net (code "64") (name "U5V") (class "Default")
      (node (ref "CN6") (pin "1") (pinfunction "VBUS_1") (pintype "passive"))
      (node (ref "D3") (pin "2") (pinfunction "A_2") (pintype "passive"))
      (node (ref "R21") (pin "2") (pinfunction "2_2") (pintype "passive"))
    )
    (net (code "65") (name "VCC") (class "Default")
      (node (ref "U1") (pin "24") (pinfunction "VDD_1_24") (pintype "passive"))
    )
    (net (code "66") (name "unconnected-(U1-BOOT0-Pad44)") (class "Default")
      (node (ref "U1") (pin "44") (pinfunction "BOOT0_44") (pintype "bidirectional"))
    )
    (net (code "67") (name "unconnected-(U1-PA1-Pad11)") (class "Default")
      (node (ref "U1") (pin "11") (pinfunction "PA1_11") (pintype "bidirectional+no_connect"))
    )
    (net (code "68") (name "unconnected-(U1-PA4-Pad14)") (class "Default")
      (node (ref "U1") (pin "14") (pinfunction "PA4_14") (pintype "bidirectional+no_connect"))
    )
    (net (code "69") (name "unconnected-(U1-PB1-Pad19)") (class "Default")
      (node (ref "U1") (pin "19") (pinfunction "PB1_19") (pintype "bidirectional+no_connect"))
    )
    (net (code "70") (name "unconnected-(U1-PB4-Pad40)") (class "Default")
      (node (ref "U1") (pin "40") (pinfunction "PB4_40") (pintype "bidirectional"))
    )
    (net (code "71") (name "unconnected-(U1-PB5-Pad41)") (class "Default")
      (node (ref "U1") (pin "41") (pinfunction "PB5_41") (pintype "bidirectional"))
    )
    (net (code "72") (name "unconnected-(U1-PB6-Pad42)") (class "Default")
      (node (ref "U1") (pin "42") (pinfunction "PB6_42") (pintype "bidirectional"))
    )
    (net (code "73") (name "unconnected-(U1-PB8-Pad45)") (class "Default")
      (node (ref "U1") (pin "45") (pinfunction "PB8_45") (pintype "bidirectional"))
    )
    (net (code "74") (name "unconnected-(U1-PB9-Pad46)") (class "Default")
      (node (ref "U1") (pin "46") (pinfunction "PB9_46") (pintype "bidirectional"))
    )
    (net (code "75") (name "unconnected-(U1-PB11-Pad22)") (class "Default")
      (node (ref "U1") (pin "22") (pinfunction "PB11_22") (pintype "bidirectional"))
    )
    (net (code "76") (name "unconnected-(U1-PC15-OSC32_OUT-Pad4)") (class "Default")
      (node (ref "U1") (pin "4") (pinfunction "PC15-OSC32_OUT_4") (pintype "bidirectional+no_connect"))
    )
  )
)
